# 3-CPUPower.net
KiCad netlist of a schematic drawn in Altium Designer
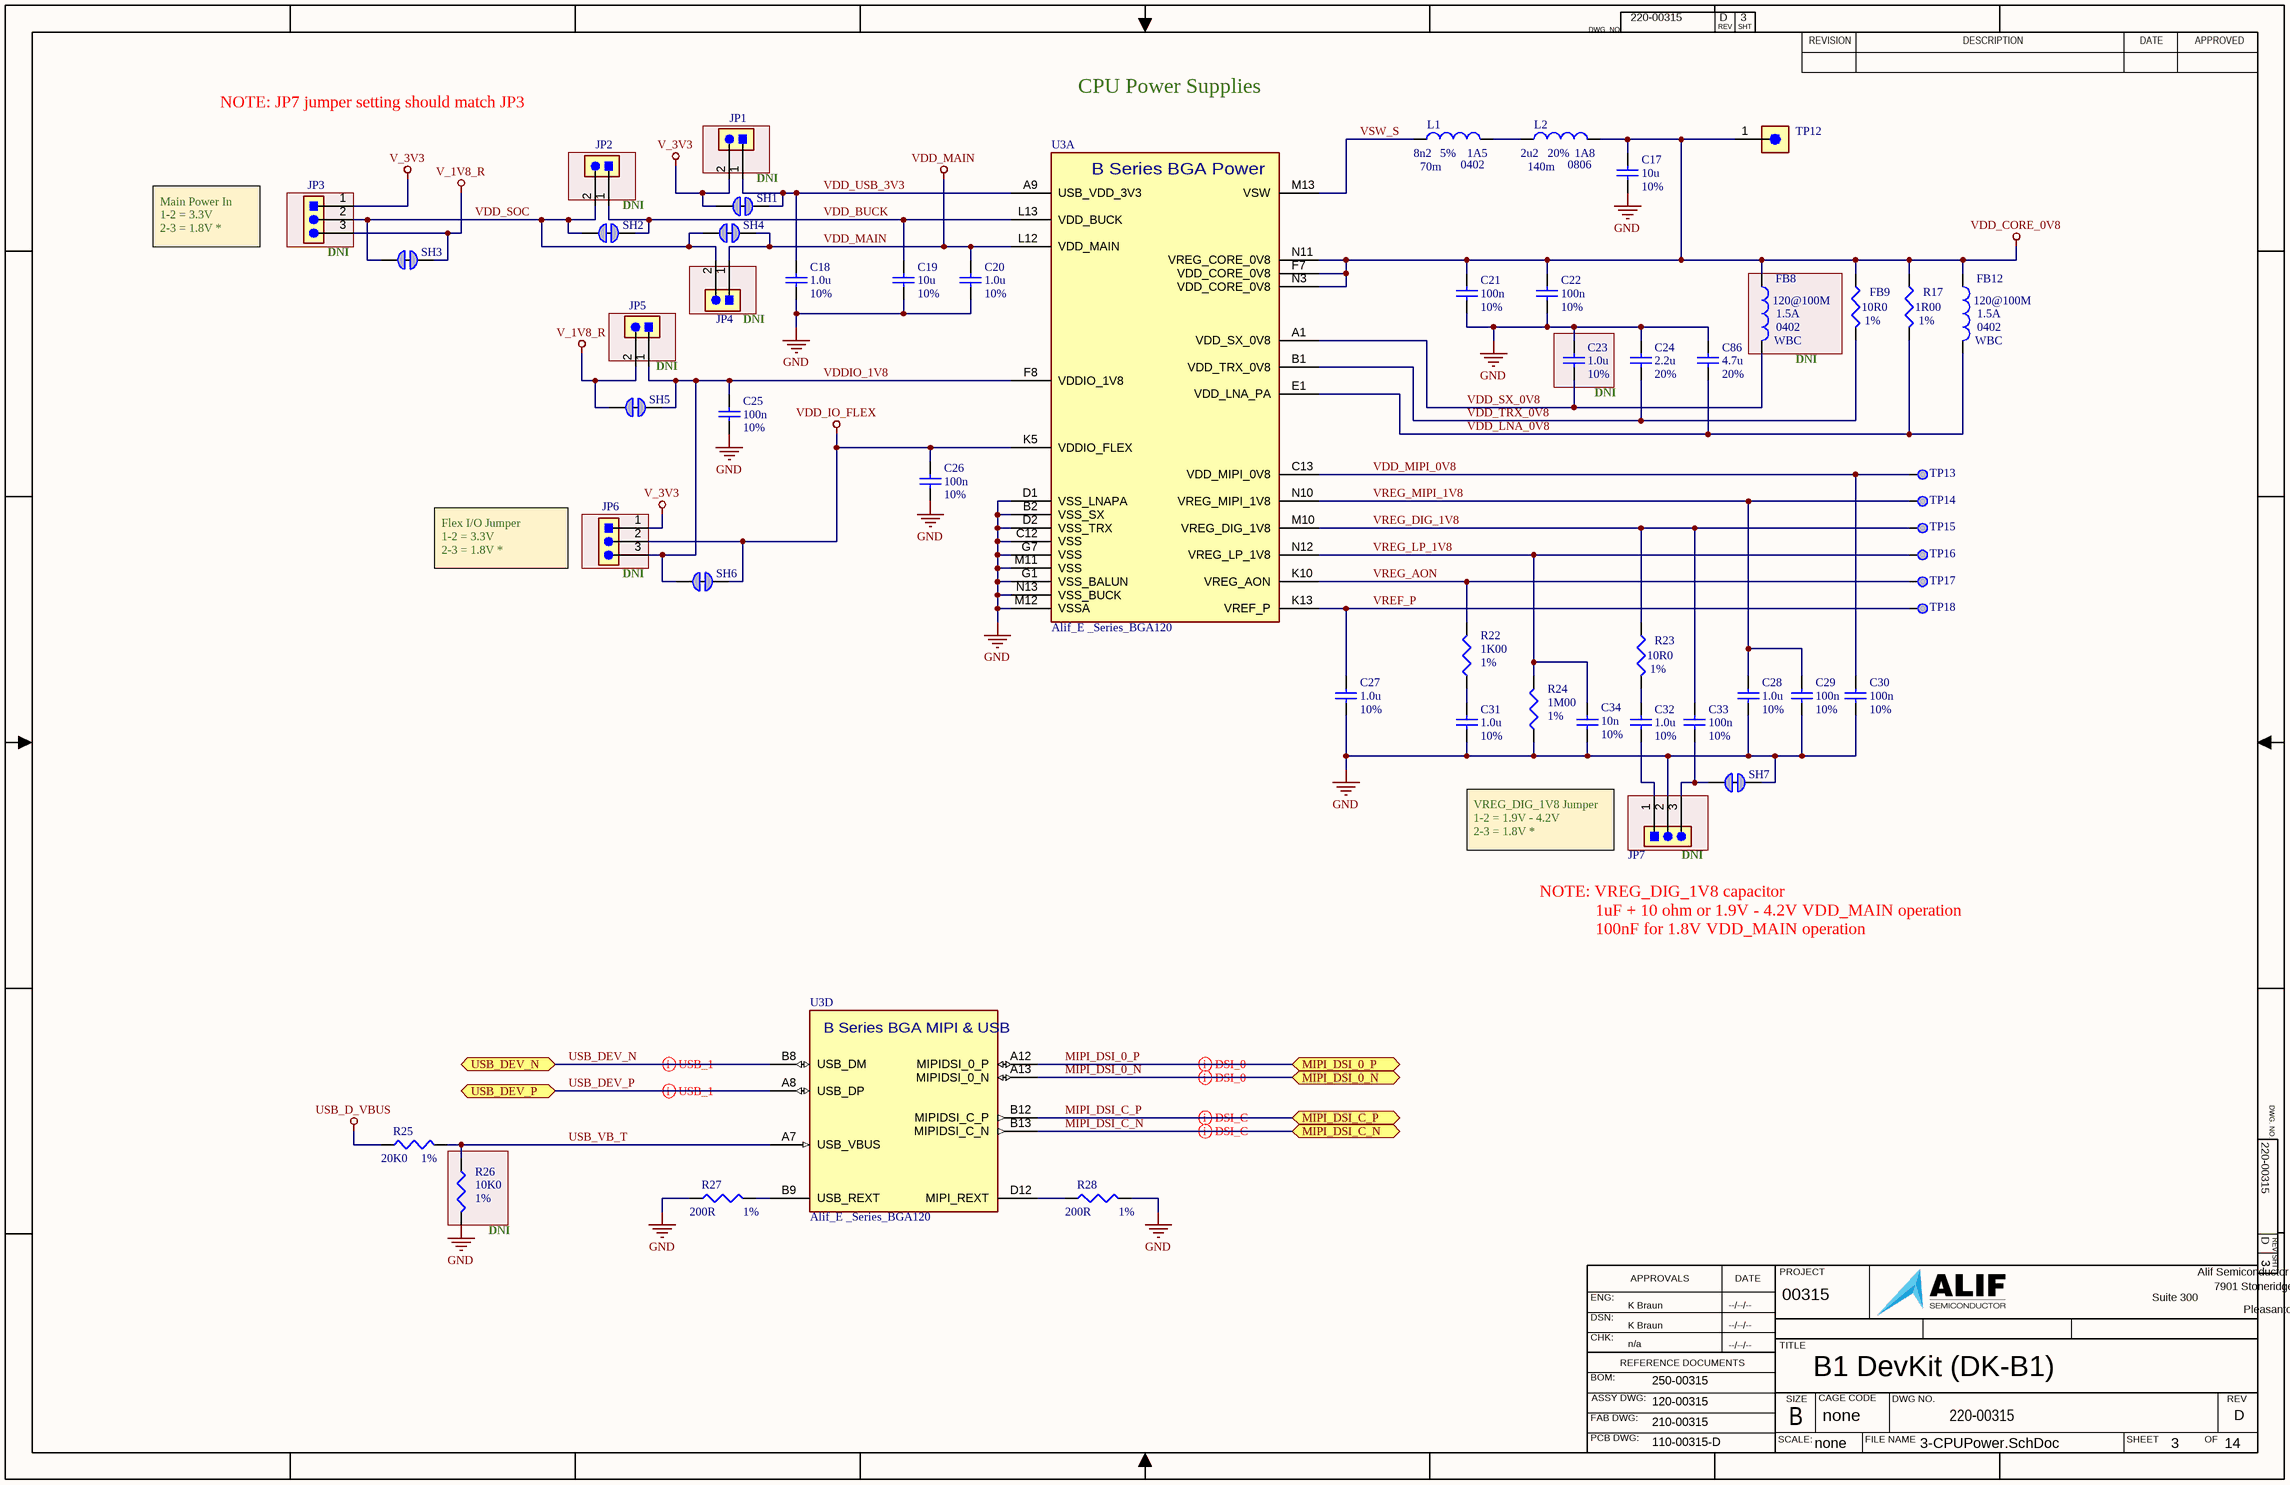
[diagram p0: 3-CPUPower.SchDoc]

(export (version "E")
  (design (tool "Eeschema 10.0.6"))
  (components
    (comp (ref "C17")
      (value "10u")
      (footprint "CAPC0402-01")
      (description "Cap,10uF,20%,10V,X5R,0402")
      (fields
        (field (name "VOLTAGE") "10V")
        (field (name "TOLERANCE") "10%")
        (field (name "Comment") "Cap")
        (field (name "PUBLISHER") "Altium Limited")
      )
      (libsource (lib "kb1") (part "Cap"))
    )
    (comp (ref "C18")
      (value "1.0u")
      (footprint "CAPC0402-01")
      (description "Cap,1.0uF,20%,25V,X5R,0402")
      (fields
        (field (name "VOLTAGE") "25V")
        (field (name "TOLERANCE") "10%")
        (field (name "Comment") "Cap")
        (field (name "PUBLISHER") "Altium Limited")
      )
      (libsource (lib "kb1") (part "Cap"))
    )
    (comp (ref "C19")
      (value "10u")
      (footprint "CAPC0402-01")
      (description "Cap,10uF,20%,10V,X5R,0402")
      (fields
        (field (name "VOLTAGE") "10V")
        (field (name "TOLERANCE") "10%")
        (field (name "Comment") "Cap")
        (field (name "PUBLISHER") "Altium Limited")
      )
      (libsource (lib "kb1") (part "Cap"))
    )
    (comp (ref "C20")
      (value "1.0u")
      (footprint "CAPC0402-01")
      (description "Cap,1.0uF,20%,25V,X5R,0402")
      (fields
        (field (name "VOLTAGE") "25V")
        (field (name "TOLERANCE") "10%")
        (field (name "Comment") "Cap")
        (field (name "PUBLISHER") "Altium Limited")
      )
      (libsource (lib "kb1") (part "Cap"))
    )
    (comp (ref "C21")
      (value "100n")
      (footprint "CAPC0402-01")
      (description "Cap,100nF,10%,50V,X7R,0402")
      (fields
        (field (name "VOLTAGE") "50V")
        (field (name "TOLERANCE") "10%")
        (field (name "Comment") "Cap")
        (field (name "PUBLISHER") "Altium Limited")
      )
      (libsource (lib "kb1") (part "Cap"))
    )
    (comp (ref "C22")
      (value "100n")
      (footprint "CAPC0402-01")
      (description "Cap,100nF,10%,50V,X7R,0402")
      (fields
        (field (name "VOLTAGE") "50V")
        (field (name "TOLERANCE") "10%")
        (field (name "Comment") "Cap")
        (field (name "PUBLISHER") "Altium Limited")
      )
      (libsource (lib "kb1") (part "Cap"))
    )
    (comp (ref "C23")
      (value "1.0u")
      (footprint "CAPC0402-01")
      (description "DNI,Cap,1.0uF,20%,25V,X5R,0402")
      (fields
        (field (name "VOLTAGE") "25V")
        (field (name "TOLERANCE") "10%")
        (field (name "Comment") "Cap")
        (field (name "PUBLISHER") "Altium Limited")
      )
      (libsource (lib "kb1") (part "Cap"))
    )
    (comp (ref "C24")
      (value "2.2u")
      (footprint "CAPC0402-01")
      (description "Cap,2.2uF,20%,25V,X5R,0402")
      (fields
        (field (name "VOLTAGE") "25V")
        (field (name "TOLERANCE") "20%")
        (field (name "Comment") "Cap_225M25VX5R0402_1")
        (field (name "PUBLISHER") "Altium Limited")
      )
      (libsource (lib "Alif-2") (part "Cap_225M25VX5R0402_1"))
    )
    (comp (ref "C25")
      (value "100n")
      (footprint "CAPC0402-01")
      (description "Cap,100nF,10%,50V,X7R,0402")
      (fields
        (field (name "VOLTAGE") "50V")
        (field (name "TOLERANCE") "10%")
        (field (name "Comment") "Cap")
        (field (name "PUBLISHER") "Altium Limited")
      )
      (libsource (lib "kb1") (part "Cap"))
    )
    (comp (ref "C26")
      (value "100n")
      (footprint "CAPC0402-01")
      (description "Cap,100nF,10%,50V,X7R,0402")
      (fields
        (field (name "VOLTAGE") "50V")
        (field (name "TOLERANCE") "10%")
        (field (name "Comment") "Cap")
        (field (name "PUBLISHER") "Altium Limited")
      )
      (libsource (lib "kb1") (part "Cap"))
    )
    (comp (ref "C27")
      (value "1.0u")
      (footprint "CAPC0402-01")
      (description "Cap,1.0uF,20%,25V,X5R,0402")
      (fields
        (field (name "VOLTAGE") "25V")
        (field (name "TOLERANCE") "10%")
        (field (name "Comment") "Cap")
        (field (name "PUBLISHER") "Altium Limited")
      )
      (libsource (lib "kb1") (part "Cap"))
    )
    (comp (ref "C28")
      (value "1.0u")
      (footprint "CAPC0402-01")
      (description "Cap,1.0uF,20%,25V,X5R,0402")
      (fields
        (field (name "VOLTAGE") "25V")
        (field (name "TOLERANCE") "10%")
        (field (name "Comment") "Cap")
        (field (name "PUBLISHER") "Altium Limited")
      )
      (libsource (lib "kb1") (part "Cap"))
    )
    (comp (ref "C29")
      (value "100n")
      (footprint "CAPC0402-01")
      (description "Cap,100nF,10%,50V,X7R,0402")
      (fields
        (field (name "VOLTAGE") "50V")
        (field (name "TOLERANCE") "10%")
        (field (name "Comment") "Cap")
        (field (name "PUBLISHER") "Altium Limited")
      )
      (libsource (lib "kb1") (part "Cap"))
    )
    (comp (ref "C30")
      (value "100n")
      (footprint "CAPC0402-01")
      (description "Cap,100nF,10%,50V,X7R,0402")
      (fields
        (field (name "VOLTAGE") "50V")
        (field (name "TOLERANCE") "10%")
        (field (name "Comment") "Cap")
        (field (name "PUBLISHER") "Altium Limited")
      )
      (libsource (lib "kb1") (part "Cap"))
    )
    (comp (ref "C31")
      (value "1.0u")
      (footprint "CAPC0402-01")
      (description "Cap,1.0uF,20%,25V,X5R,0402")
      (fields
        (field (name "VOLTAGE") "25V")
        (field (name "TOLERANCE") "10%")
        (field (name "Comment") "Cap")
        (field (name "PUBLISHER") "Altium Limited")
      )
      (libsource (lib "kb1") (part "Cap"))
    )
    (comp (ref "C32")
      (value "1.0u")
      (footprint "CAPC0402-01")
      (description "Cap,1.0uF,20%,25V,X5R,0402")
      (fields
        (field (name "VOLTAGE") "25V")
        (field (name "TOLERANCE") "10%")
        (field (name "Comment") "Cap")
        (field (name "PUBLISHER") "Altium Limited")
      )
      (libsource (lib "kb1") (part "Cap"))
    )
    (comp (ref "C33")
      (value "100n")
      (footprint "CAPC0402-01")
      (description "Cap,100nF,10%,50V,X7R,0402")
      (fields
        (field (name "VOLTAGE") "50V")
        (field (name "TOLERANCE") "10%")
        (field (name "Comment") "Cap")
        (field (name "PUBLISHER") "Altium Limited")
      )
      (libsource (lib "kb1") (part "Cap"))
    )
    (comp (ref "C34")
      (value "10n")
      (footprint "CAPC0402-01")
      (description "Cap,10nF,10%,50V,X7R,0402")
      (fields
        (field (name "VOLTAGE") "50V")
        (field (name "TOLERANCE") "10%")
        (field (name "Comment") "Cap")
        (field (name "PUBLISHER") "Altium Limited")
      )
      (libsource (lib "kb1") (part "Cap"))
    )
    (comp (ref "C86")
      (value "4.7u")
      (footprint "CAPC0402-01")
      (description "Cap,4.7uF,20%,10V,X5R,0402")
      (fields
        (field (name "VOLTAGE") "10V")
        (field (name "TOLERANCE") "20%")
        (field (name "Comment") "Cap")
        (field (name "PUBLISHER") "Altium Limited")
      )
      (libsource (lib "Alif-2") (part "Cap_225M25VX5R0402_1"))
    )
    (comp (ref "FB8")
      (value "WBC")
      (footprint "FB_0402_MuRata_as_R0402")
      (description "DNI,Ind,WidebandChoke,1.5A,120ohm@100MHz,95mOhm,0402")
      (fields
        (field (name "TOLERANCE") "30%")
        (field (name "IMPEDANCE") "120@100M")
        (field (name "PCB_FOOTPRINT") "0402")
        (field (name "RMS_CURRENT") "1.5A")
        (field (name "Comment") "Ind_WBC_1A5_120@100M0402_1")
        (field (name "PUBLISHER") "Altium Limited")
      )
      (libsource (lib "Alif2") (part "Ind_WBC_1A5_120@100M0402_1"))
    )
    (comp (ref "FB9")
      (value "10R0")
      (footprint "RESC0402-01")
      (description "Res,10R0,1%,100ppm,0402")
      (fields
        (field (name "TOLERANCE") "1%")
        (field (name "Comment") "Res3")
        (field (name "PUBLISHER") "Altium Limited")
      )
      (libsource (lib "kb1") (part "Res3"))
    )
    (comp (ref "FB12")
      (value "WBC")
      (footprint "FB_0402_MuRata_as_R0402")
      (description "Ind,WidebandChoke,1.5A,120ohm@100MHz,95mOhm,0402")
      (fields
        (field (name "TOLERANCE") "30%")
        (field (name "IMPEDANCE") "120@100M")
        (field (name "PCB_FOOTPRINT") "0402")
        (field (name "RMS_CURRENT") "1.5A")
        (field (name "Comment") "Ind_WBC_1A5_120@100M0402_1")
        (field (name "PUBLISHER") "Altium Limited")
      )
      (libsource (lib "Alif2") (part "Ind_WBC_1A5_120@100M0402_1"))
    )
    (comp (ref "JP1")
      (value "TSW-102-07-G-S")
      (footprint "CONN_77311-146-02LF_AMP_HDR_1x2_2.5MM_STRT_no#D")
      (fields (field (name "MANUFACTURER") "Samtec"))
      (libsource (lib "") (part "Hdr_M_1X2_2M54_STRT_UNSHROUD_1"))
    )
    (comp (ref "JP2")
      (value "TSW-102-07-G-S")
      (footprint "CONN_77311-146-02LF_AMP_HDR_1x2_2.5MM_STRT_no#D")
      (fields (field (name "MANUFACTURER") "Samtec"))
      (libsource (lib "") (part "Hdr_M_1X2_2M54_STRT_UNSHROUD_1"))
    )
    (comp (ref "JP3")
      (value "TSW-103-07-G-S")
      (footprint "CONN_HDR_1X3_STRT_0.100_no3D")
      (fields (field (name "MANUFACTURER") "Samtec"))
      (libsource (lib "") (part "Hdr_M_1X3_2M54_STRT_UNSHROUD_1"))
    )
    (comp (ref "JP4")
      (value "TSW-102-07-G-S")
      (footprint "CONN_77311-146-02LF_AMP_HDR_1x2_2.5MM_STRT_no#D")
      (fields (field (name "MANUFACTURER") "Samtec"))
      (libsource (lib "Alif-2") (part "Hdr_M_1X2_2M54_STRT_UNSHROUD"))
    )
    (comp (ref "JP5")
      (value "TSW-102-07-G-S")
      (footprint "CONN_77311-146-02LF_AMP_HDR_1x2_2.5MM_STRT_no#D")
      (fields (field (name "MANUFACTURER") "Samtec"))
      (libsource (lib "") (part "Hdr_M_1X2_2M54_STRT_UNSHROUD_1"))
    )
    (comp (ref "JP6")
      (value "TSW-103-07-G-S")
      (footprint "CONN_HDR_1X3_STRT_0.100_no3D")
      (fields (field (name "MANUFACTURER") "Samtec"))
      (libsource (lib "") (part "Hdr_M_1X3_2M54_STRT_UNSHROUD_1"))
    )
    (comp (ref "JP7")
      (value "TSW-103-07-G-S")
      (footprint "CONN_HDR_1X3_STRT_0.100_no3D")
      (fields (field (name "MANUFACTURER") "Samtec"))
      (libsource (lib "Alif-2") (part "Hdr_M_1X3_2M54_STRT_UNSHROUD"))
    )
    (comp (ref "L1")
      (value "8n2")
      (footprint "IND_WE-KI_0402")
      (description "Ind,Unshielded,8.2nH,<5%,1.5A,<70mOhm, SRF > 4GHz, 0402")
      (fields
        (field (name "PCB_FOOTPRINT") "0402")
        (field (name "DCR") "70m")
        (field (name "RMS_CURRENT") "1A5")
        (field (name "TOLERANCE") "5%")
        (field (name "Comment") "Inductor")
        (field (name "PUBLISHER") "Altium Limited")
      )
      (libsource (lib "Alif-2") (part "Inductor"))
    )
    (comp (ref "L2")
      (value "2u2")
      (footprint "IND_0806_2016_SAM")
      (description "Ind,Shielded,Metal Comp,2.2uH,20%,1.8A,<140mOhm,0806(2016)")
      (fields
        (field (name "PCB_FOOTPRINT") "0806")
        (field (name "DCR") "140m")
        (field (name "RMS_CURRENT") "1A8")
        (field (name "TOLERANCE") "20%")
        (field (name "Comment") "Inductor")
        (field (name "PUBLISHER") "Altium Limited")
      )
      (libsource (lib "Alif-2") (part "Inductor"))
    )
    (comp (ref "R17")
      (value "1R00")
      (footprint "RESC0402-01")
      (description "Res,1R00,1%,100ppm,0402")
      (fields
        (field (name "TOLERANCE") "1%")
        (field (name "Comment") "Res3")
        (field (name "PUBLISHER") "Altium Limited")
      )
      (libsource (lib "kb1") (part "Res3"))
    )
    (comp (ref "R22")
      (value "1K00")
      (footprint "RESC0402-01")
      (description "Res,1K00,1%,100ppm,0402")
      (fields
        (field (name "TOLERANCE") "1%")
        (field (name "Comment") "Res3")
        (field (name "PUBLISHER") "Altium Limited")
      )
      (libsource (lib "kb1") (part "Res3"))
    )
    (comp (ref "R23")
      (value "10R0")
      (footprint "RESC0402-01")
      (description "Res,10R0,1%,100ppm,0402")
      (fields
        (field (name "TOLERANCE") "1%")
        (field (name "Comment") "Res3")
        (field (name "PUBLISHER") "Altium Limited")
      )
      (libsource (lib "kb1") (part "Res3"))
    )
    (comp (ref "R24")
      (value "1M00")
      (footprint "RESC0402-01")
      (description "Res,1M00,1%,100ppm,0402")
      (fields
        (field (name "TOLERANCE") "1%")
        (field (name "Comment") "Res3")
        (field (name "PUBLISHER") "Altium Limited")
      )
      (libsource (lib "kb1") (part "Res3"))
    )
    (comp (ref "R25")
      (value "20K0")
      (footprint "RESC0402-01")
      (description "Res,20K0,1%,100ppm,0402")
      (fields
        (field (name "TOLERANCE") "1%")
        (field (name "Comment") "Res3")
        (field (name "PUBLISHER") "Altium Limited")
      )
      (libsource (lib "kb1") (part "Res3"))
    )
    (comp (ref "R26")
      (value "10K0")
      (footprint "RESC0402-01")
      (description "DNI,Res,10K0,1%,100ppm,0402")
      (fields
        (field (name "TOLERANCE") "1%")
        (field (name "Comment") "Res3")
        (field (name "PUBLISHER") "Altium Limited")
      )
      (libsource (lib "kb1") (part "Res3"))
    )
    (comp (ref "R27")
      (value "200R")
      (footprint "RESC0402-01")
      (description "Res,200R,1%,100ppm,0402")
      (fields
        (field (name "TOLERANCE") "1%")
        (field (name "Comment") "Res3")
        (field (name "PUBLISHER") "Altium Limited")
      )
      (libsource (lib "kb1") (part "Res3"))
    )
    (comp (ref "R28")
      (value "200R")
      (footprint "RESC0402-01")
      (description "Res,200R,1%,100ppm,0402")
      (fields
        (field (name "TOLERANCE") "1%")
        (field (name "Comment") "Res3")
        (field (name "PUBLISHER") "Altium Limited")
      )
      (libsource (lib "kb1") (part "Res3"))
    )
    (comp (ref "SH1")
      (value "SolderJumperShorted_Small")
      (footprint "Solderbridge_Shorted")
      (description "DNI,Solderable Jumper,Shorted")
      (fields (field (name "PUBLISHER") "Altium Limited"))
      (libsource (lib "Alif-2") (part "SolderJumperShorted_Small"))
    )
    (comp (ref "SH2")
      (value "SolderJumperShorted_Small")
      (footprint "Solderbridge_Shorted")
      (description "DNI,Solderable Jumper,Shorted")
      (fields (field (name "PUBLISHER") "Altium Limited"))
      (libsource (lib "Alif-2") (part "SolderJumperShorted_Small"))
    )
    (comp (ref "SH3")
      (value "SolderJumperShorted_Small")
      (footprint "Solderbridge_Shorted")
      (description "DNI,Solderable Jumper,Shorted")
      (fields (field (name "PUBLISHER") "Altium Limited"))
      (libsource (lib "Alif-2") (part "SolderJumperShorted_Small"))
    )
    (comp (ref "SH4")
      (value "SolderJumperShorted_Small")
      (footprint "Solderbridge_Shorted")
      (description "DNI,Solderable Jumper,Shorted")
      (fields (field (name "PUBLISHER") "Altium Limited"))
      (libsource (lib "Alif-2") (part "SolderJumperShorted_Small"))
    )
    (comp (ref "SH5")
      (value "SolderJumperShorted_Small")
      (footprint "Solderbridge_Shorted")
      (description "DNI,Solderable Jumper,Shorted")
      (fields (field (name "PUBLISHER") "Altium Limited"))
      (libsource (lib "Alif-2") (part "SolderJumperShorted_Small"))
    )
    (comp (ref "SH6")
      (value "SolderJumperShorted_Small")
      (footprint "Solderbridge_Shorted")
      (description "DNI,Solderable Jumper,Shorted")
      (fields (field (name "PUBLISHER") "Altium Limited"))
      (libsource (lib "Alif-2") (part "SolderJumperShorted_Small"))
    )
    (comp (ref "SH7")
      (value "SolderJumperShorted_Small")
      (footprint "Solderbridge_Shorted")
      (description "DNI,Solderable Jumper,Shorted")
      (fields (field (name "PUBLISHER") "Altium Limited"))
      (libsource (lib "Alif-2") (part "SolderJumperShorted_Small"))
    )
    (comp (ref "TP12")
      (value "TSW-101-07-G-S")
      (footprint "CONN_77311-146-01LF_AMP_HDR_1X1_2.5MM_STRT_No3D")
      (fields (field (name "MANUFACTURER") "Samtec"))
      (libsource (lib "Alif-2") (part "Hdr_M_1X1_2M54_STRT_UNSHROUD"))
    )
    (comp (ref "TP13")
      (value "TP_SMPAD")
      (footprint "TP_30_RND")
      (description "Test Point, SMT Pad,--not a BOM item--")
      (libsource (lib "Alif-2") (part "TP_SMPAD"))
    )
    (comp (ref "TP14")
      (value "TP_SMPAD")
      (footprint "TP_30_RND")
      (description "Test Point, SMT Pad,--not a BOM item--")
      (libsource (lib "Alif-2") (part "TP_SMPAD"))
    )
    (comp (ref "TP15")
      (value "TP_SMPAD")
      (footprint "TP_30_RND")
      (description "Test Point, SMT Pad,--not a BOM item--")
      (libsource (lib "Alif-2") (part "TP_SMPAD"))
    )
    (comp (ref "TP16")
      (value "TP_SMPAD")
      (footprint "TP_30_RND")
      (description "Test Point, SMT Pad,--not a BOM item--")
      (libsource (lib "Alif-2") (part "TP_SMPAD"))
    )
    (comp (ref "TP17")
      (value "TP_SMPAD")
      (footprint "TP_30_RND")
      (description "Test Point, SMT Pad,--not a BOM item--")
      (libsource (lib "Alif-2") (part "TP_SMPAD"))
    )
    (comp (ref "TP18")
      (value "TP_SMPAD")
      (footprint "TP_30_RND")
      (description "Test Point, SMT Pad,--not a BOM item--")
      (libsource (lib "Alif-2") (part "TP_SMPAD"))
    )
    (comp (ref "U3")
      (value "Alif_E _Series_BGA120")
      (footprint "BGA120_socket-NO_SOCK_3D")
      (description "IC,Alif Spark B1 MCU, Rev A5 silicon,BGA120")
      (libsource (lib "Alif") (part "SPARK_B1_120BGA_A5"))
    )
  )
  (nets
    (net (code "1") (name "/MIPI_DSI_0_N") (class "Default")
      (node (ref "U3") (pin "A13") (pinfunction "MIPIDSI_0_N_A13") (pintype "bidirectional"))
    )
    (net (code "2") (name "/MIPI_DSI_0_P") (class "Default")
      (node (ref "U3") (pin "A12") (pinfunction "MIPIDSI_0_P_A12") (pintype "bidirectional"))
    )
    (net (code "3") (name "/MIPI_DSI_C_N") (class "Default")
      (node (ref "U3") (pin "B13") (pinfunction "MIPIDSI_C_N_B13") (pintype "output"))
    )
    (net (code "4") (name "/MIPI_DSI_C_P") (class "Default")
      (node (ref "U3") (pin "B12") (pinfunction "MIPIDSI_C_P_B12") (pintype "output"))
    )
    (net (code "5") (name "/USB_DEV_N") (class "Default")
      (node (ref "U3") (pin "B8") (pinfunction "USB_DM_B8") (pintype "bidirectional"))
    )
    (net (code "6") (name "/USB_DEV_P") (class "Default")
      (node (ref "U3") (pin "A8") (pinfunction "USB_DP_A8") (pintype "bidirectional"))
    )
    (net (code "7") (name "/USB_VB_T") (class "Default")
      (node (ref "R25") (pin "2") (pinfunction "2_2") (pintype "passive"))
      (node (ref "R26") (pin "1") (pinfunction "1_1") (pintype "passive"))
      (node (ref "U3") (pin "A7") (pinfunction "USB_VBUS_A7") (pintype "input"))
    )
    (net (code "8") (name "/VDDIO_1V8") (class "Default")
      (node (ref "C25") (pin "2") (pinfunction "2_2") (pintype "passive"))
      (node (ref "JP5") (pin "1") (pinfunction "1_1") (pintype "passive"))
      (node (ref "JP6") (pin "3") (pinfunction "3_3") (pintype "passive"))
      (node (ref "SH5") (pin "2") (pinfunction "2_2") (pintype "passive"))
      (node (ref "SH6") (pin "1") (pinfunction "1_1") (pintype "passive"))
      (node (ref "U3") (pin "F8") (pinfunction "VDDIO_1V8_F8") (pintype "power_in"))
    )
    (net (code "9") (name "/VDD_BUCK") (class "Default")
      (node (ref "C19") (pin "2") (pinfunction "2_2") (pintype "passive"))
      (node (ref "JP2") (pin "1") (pinfunction "1_1") (pintype "passive"))
      (node (ref "SH2") (pin "2") (pinfunction "2_2") (pintype "passive"))
      (node (ref "U3") (pin "L13") (pinfunction "VDD_BUCK_L13") (pintype "power_in"))
    )
    (net (code "10") (name "/VDD_LNA_0V8") (class "Default")
      (node (ref "C86") (pin "1") (pinfunction "1_1") (pintype "passive"))
      (node (ref "FB12") (pin "2") (pinfunction "2_2") (pintype "passive"))
      (node (ref "R17") (pin "1") (pinfunction "1_1") (pintype "passive"))
      (node (ref "U3") (pin "E1") (pinfunction "VDD_LNA_PA_E1") (pintype "passive"))
    )
    (net (code "11") (name "/VDD_MIPI_0V8") (class "Default")
      (node (ref "C30") (pin "2") (pinfunction "2_2") (pintype "passive"))
      (node (ref "TP13") (pin "1") (pinfunction "1_1") (pintype "passive"))
      (node (ref "U3") (pin "C13") (pinfunction "VDD_MIPI_0V8_C13") (pintype "power_in"))
    )
    (net (code "12") (name "/VDD_SOC") (class "Default")
      (node (ref "JP2") (pin "2") (pinfunction "2_2") (pintype "passive"))
      (node (ref "JP3") (pin "2") (pinfunction "2_2") (pintype "passive"))
      (node (ref "JP4") (pin "2") (pinfunction "2_2") (pintype "passive"))
      (node (ref "SH2") (pin "1") (pinfunction "1_1") (pintype "passive"))
      (node (ref "SH3") (pin "1") (pinfunction "1_1") (pintype "passive"))
      (node (ref "SH4") (pin "1") (pinfunction "1_1") (pintype "passive"))
    )
    (net (code "13") (name "/VDD_SX_0V8") (class "Default")
      (node (ref "C23") (pin "1") (pinfunction "1_1") (pintype "passive"))
      (node (ref "FB8") (pin "2") (pinfunction "2_2") (pintype "passive"))
      (node (ref "U3") (pin "A1") (pinfunction "VDD_SX_0V8_A1") (pintype "power_in"))
    )
    (net (code "14") (name "/VDD_TRX_0V8") (class "Default")
      (node (ref "C24") (pin "1") (pinfunction "1_1") (pintype "passive"))
      (node (ref "FB9") (pin "1") (pinfunction "1_1") (pintype "passive"))
      (node (ref "U3") (pin "B1") (pinfunction "VDD_TRX_0V8_B1") (pintype "power_in"))
    )
    (net (code "15") (name "/VDD_USB_3V3") (class "Default")
      (node (ref "C18") (pin "2") (pinfunction "2_2") (pintype "passive"))
      (node (ref "JP1") (pin "1") (pinfunction "1_1") (pintype "passive"))
      (node (ref "SH1") (pin "2") (pinfunction "2_2") (pintype "passive"))
      (node (ref "U3") (pin "A9") (pinfunction "USB_VDD_3V3_A9") (pintype "power_in"))
    )
    (net (code "16") (name "/VREF_P") (class "Default")
      (node (ref "C27") (pin "2") (pinfunction "2_2") (pintype "passive"))
      (node (ref "TP18") (pin "1") (pinfunction "1_1") (pintype "passive"))
      (node (ref "U3") (pin "K13") (pinfunction "VREF_P_K13") (pintype "passive"))
    )
    (net (code "17") (name "/VREG_AON") (class "Default")
      (node (ref "R22") (pin "2") (pinfunction "2_2") (pintype "passive"))
      (node (ref "TP17") (pin "1") (pinfunction "1_1") (pintype "passive"))
      (node (ref "U3") (pin "K10") (pinfunction "VREG_AON_K10") (pintype "power_in"))
    )
    (net (code "18") (name "/VREG_DIG_1V8") (class "Default")
      (node (ref "C33") (pin "2") (pinfunction "2_2") (pintype "passive"))
      (node (ref "R23") (pin "2") (pinfunction "2_2") (pintype "passive"))
      (node (ref "TP15") (pin "1") (pinfunction "1_1") (pintype "passive"))
      (node (ref "U3") (pin "M10") (pinfunction "VREG_DIG_1V8_M10") (pintype "power_in"))
    )
    (net (code "19") (name "/VREG_LP_1V8") (class "Default")
      (node (ref "C34") (pin "1") (pinfunction "1_1") (pintype "passive"))
      (node (ref "R24") (pin "2") (pinfunction "2_2") (pintype "passive"))
      (node (ref "TP16") (pin "1") (pinfunction "1_1") (pintype "passive"))
      (node (ref "U3") (pin "N12") (pinfunction "VREG_LP_1V8_N12") (pintype "power_in"))
    )
    (net (code "20") (name "/VREG_MIPI_1V8") (class "Default")
      (node (ref "C28") (pin "2") (pinfunction "2_2") (pintype "passive"))
      (node (ref "C29") (pin "2") (pinfunction "2_2") (pintype "passive"))
      (node (ref "TP14") (pin "1") (pinfunction "1_1") (pintype "passive"))
      (node (ref "U3") (pin "N10") (pinfunction "VREG_MIPI_1V8_N10") (pintype "power_in"))
    )
    (net (code "21") (name "/VSW_S") (class "Default")
      (node (ref "L1") (pin "1") (pinfunction "1_1") (pintype "passive"))
      (node (ref "U3") (pin "M13") (pinfunction "VSW_M13") (pintype "passive"))
    )
    (net (code "22") (name "GND") (class "Default")
      (node (ref "C17") (pin "1") (pinfunction "1_1") (pintype "passive"))
      (node (ref "C18") (pin "1") (pinfunction "1_1") (pintype "passive"))
      (node (ref "C19") (pin "1") (pinfunction "1_1") (pintype "passive"))
      (node (ref "C20") (pin "1") (pinfunction "1_1") (pintype "passive"))
      (node (ref "C21") (pin "1") (pinfunction "1_1") (pintype "passive"))
      (node (ref "C22") (pin "1") (pinfunction "1_1") (pintype "passive"))
      (node (ref "C23") (pin "2") (pinfunction "2_2") (pintype "passive"))
      (node (ref "C24") (pin "2") (pinfunction "2_2") (pintype "passive"))
      (node (ref "C25") (pin "1") (pinfunction "1_1") (pintype "passive"))
      (node (ref "C26") (pin "1") (pinfunction "1_1") (pintype "passive"))
      (node (ref "C27") (pin "1") (pinfunction "1_1") (pintype "passive"))
      (node (ref "C28") (pin "1") (pinfunction "1_1") (pintype "passive"))
      (node (ref "C29") (pin "1") (pinfunction "1_1") (pintype "passive"))
      (node (ref "C30") (pin "1") (pinfunction "1_1") (pintype "passive"))
      (node (ref "C31") (pin "1") (pinfunction "1_1") (pintype "passive"))
      (node (ref "C34") (pin "2") (pinfunction "2_2") (pintype "passive"))
      (node (ref "C86") (pin "2") (pinfunction "2_2") (pintype "passive"))
      (node (ref "JP7") (pin "2") (pinfunction "2_2") (pintype "passive"))
      (node (ref "R24") (pin "1") (pinfunction "1_1") (pintype "passive"))
      (node (ref "R26") (pin "2") (pinfunction "2_2") (pintype "passive"))
      (node (ref "R27") (pin "1") (pinfunction "1_1") (pintype "passive"))
      (node (ref "R28") (pin "2") (pinfunction "2_2") (pintype "passive"))
      (node (ref "SH7") (pin "2") (pinfunction "2_2") (pintype "passive"))
      (node (ref "U3") (pin "B2") (pinfunction "VSS_SX_B2") (pintype "power_in"))
      (node (ref "U3") (pin "C12") (pinfunction "VSS_C12") (pintype "power_in"))
      (node (ref "U3") (pin "D1") (pinfunction "VSS_LNAPA_D1") (pintype "power_in"))
      (node (ref "U3") (pin "D2") (pinfunction "VSS_TRX_D2") (pintype "passive"))
      (node (ref "U3") (pin "G1") (pinfunction "VSS_BALUN_G1") (pintype "passive"))
      (node (ref "U3") (pin "G7") (pinfunction "VSS_G7") (pintype "power_in"))
      (node (ref "U3") (pin "M11") (pinfunction "VSS_M11") (pintype "power_in"))
      (node (ref "U3") (pin "M12") (pinfunction "VSSA_M12") (pintype "power_in"))
      (node (ref "U3") (pin "N13") (pinfunction "VSS_BUCK_N13") (pintype "power_in"))
    )
    (net (code "23") (name "Net-(C31-Pad2)") (class "Default")
      (node (ref "C31") (pin "2") (pinfunction "2_2") (pintype "passive"))
      (node (ref "R22") (pin "1") (pinfunction "1_1") (pintype "passive"))
    )
    (net (code "24") (name "Net-(C32-Pad1)") (class "Default")
      (node (ref "C32") (pin "1") (pinfunction "1_1") (pintype "passive"))
      (node (ref "JP7") (pin "1") (pinfunction "1_1") (pintype "passive"))
    )
    (net (code "25") (name "Net-(C32-Pad2)") (class "Default")
      (node (ref "C32") (pin "2") (pinfunction "2_2") (pintype "passive"))
      (node (ref "R23") (pin "1") (pinfunction "1_1") (pintype "passive"))
    )
    (net (code "26") (name "Net-(C33-Pad1)") (class "Default")
      (node (ref "C33") (pin "1") (pinfunction "1_1") (pintype "passive"))
      (node (ref "JP7") (pin "3") (pinfunction "3_3") (pintype "passive"))
      (node (ref "SH7") (pin "1") (pinfunction "1_1") (pintype "passive"))
    )
    (net (code "27") (name "Net-(L1-Pad2)") (class "Default")
      (node (ref "L1") (pin "2") (pinfunction "2_2") (pintype "passive"))
      (node (ref "L2") (pin "1") (pinfunction "1_1") (pintype "passive"))
    )
    (net (code "28") (name "Net-(U3D-MIPI_REXT)") (class "Default")
      (node (ref "R28") (pin "1") (pinfunction "1_1") (pintype "passive"))
      (node (ref "U3") (pin "D12") (pinfunction "MIPI_REXT_D12") (pintype "passive"))
    )
    (net (code "29") (name "Net-(U3D-USB_REXT)") (class "Default")
      (node (ref "R27") (pin "2") (pinfunction "2_2") (pintype "passive"))
      (node (ref "U3") (pin "B9") (pinfunction "USB_REXT_B9") (pintype "passive"))
    )
    (net (code "30") (name "USB_D_VBUS") (class "Default")
      (node (ref "R25") (pin "1") (pinfunction "1_1") (pintype "passive"))
    )
    (net (code "31") (name "VDD_CORE_0V8") (class "Default")
      (node (ref "C17") (pin "2") (pinfunction "2_2") (pintype "passive"))
      (node (ref "C21") (pin "2") (pinfunction "2_2") (pintype "passive"))
      (node (ref "C22") (pin "2") (pinfunction "2_2") (pintype "passive"))
      (node (ref "FB12") (pin "1") (pinfunction "1_1") (pintype "passive"))
      (node (ref "FB8") (pin "1") (pinfunction "1_1") (pintype "passive"))
      (node (ref "FB9") (pin "2") (pinfunction "2_2") (pintype "passive"))
      (node (ref "L2") (pin "2") (pinfunction "2_2") (pintype "passive"))
      (node (ref "R17") (pin "2") (pinfunction "2_2") (pintype "passive"))
      (node (ref "TP12") (pin "1") (pinfunction "1_1") (pintype "passive"))
      (node (ref "U3") (pin "F7") (pinfunction "VDD_CORE_0V8_F7") (pintype "power_in"))
      (node (ref "U3") (pin "N11") (pinfunction "VREG_CORE_0V8_N11") (pintype "power_in"))
      (node (ref "U3") (pin "N3") (pinfunction "VDD_CORE_0V8_N3") (pintype "passive"))
    )
    (net (code "32") (name "VDD_IO_FLEX") (class "Default")
      (node (ref "C26") (pin "2") (pinfunction "2_2") (pintype "passive"))
      (node (ref "JP6") (pin "2") (pinfunction "2_2") (pintype "passive"))
      (node (ref "SH6") (pin "2") (pinfunction "2_2") (pintype "passive"))
      (node (ref "U3") (pin "K5") (pinfunction "VDDIO_FLEX_K5") (pintype "power_in"))
    )
    (net (code "33") (name "VDD_MAIN") (class "Default")
      (node (ref "C20") (pin "2") (pinfunction "2_2") (pintype "passive"))
      (node (ref "JP4") (pin "1") (pinfunction "1_1") (pintype "passive"))
      (node (ref "SH4") (pin "2") (pinfunction "2_2") (pintype "passive"))
      (node (ref "U3") (pin "L12") (pinfunction "VDD_MAIN_L12") (pintype "power_in"))
    )
    (net (code "34") (name "V_1V8_R") (class "Default")
      (node (ref "JP3") (pin "3") (pinfunction "3_3") (pintype "passive"))
      (node (ref "JP5") (pin "2") (pinfunction "2_2") (pintype "passive"))
      (node (ref "SH3") (pin "2") (pinfunction "2_2") (pintype "passive"))
      (node (ref "SH5") (pin "1") (pinfunction "1_1") (pintype "passive"))
    )
    (net (code "35") (name "V_3V3") (class "Default")
      (node (ref "JP1") (pin "2") (pinfunction "2_2") (pintype "passive"))
      (node (ref "JP3") (pin "1") (pinfunction "1_1") (pintype "passive"))
      (node (ref "JP6") (pin "1") (pinfunction "1_1") (pintype "passive"))
      (node (ref "SH1") (pin "1") (pinfunction "1_1") (pintype "passive"))
    )
  )
)
